# board.net
KiCad netlist of a schematic drawn in EAGLE
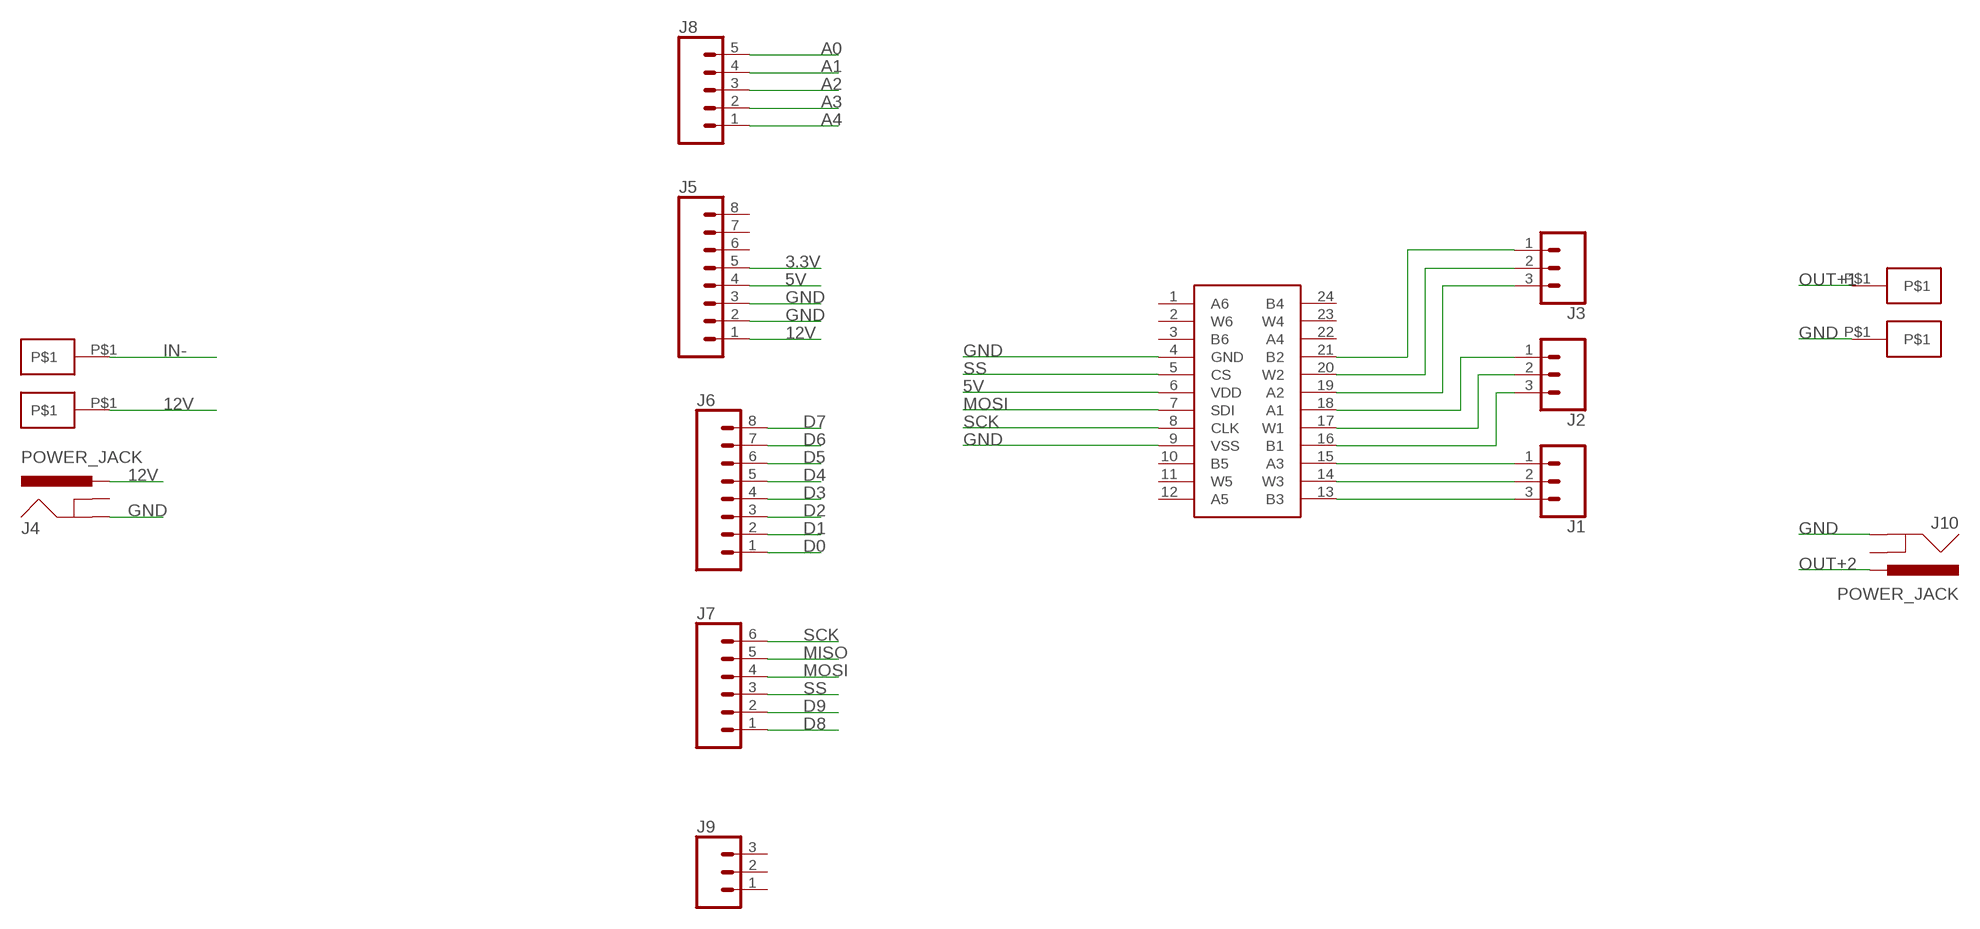
[diagram p0: schematic, sheet 1]

(export (version "E")
  (design (tool "Eeschema 10.0.6"))
  (components
    (comp (ref "J1")
      (value "CONN_03")
      (footprint "eagle-import:1X03")
      (libsource (lib "eagle-import") (part "CONN_03"))
    )
    (comp (ref "J2")
      (value "CONN_03")
      (footprint "eagle-import:1X03")
      (libsource (lib "eagle-import") (part "CONN_03"))
    )
    (comp (ref "J3")
      (value "CONN_03")
      (footprint "eagle-import:1X03")
      (libsource (lib "eagle-import") (part "CONN_03"))
    )
    (comp (ref "J4")
      (value "POWER_JACK")
      (footprint "eagle-import:POWER_JACK_PTH")
      (libsource (lib "eagle-import") (part "POWER_JACK"))
    )
    (comp (ref "J5")
      (value "CONN_08\"")
      (footprint "eagle-import:1X08")
      (libsource (lib "eagle-import") (part "CONN_08{dblquote}"))
    )
    (comp (ref "J6")
      (value "CONN_08\"")
      (footprint "eagle-import:1X08")
      (libsource (lib "eagle-import") (part "CONN_08{dblquote}"))
    )
    (comp (ref "J7")
      (value "CONN_06SILK_FEMALE_PTH")
      (footprint "eagle-import:1X06")
      (libsource (lib "eagle-import") (part "CONN_06SILK_FEMALE_PTH"))
    )
    (comp (ref "J8")
      (value "CONN_05")
      (footprint "eagle-import:1X05")
      (libsource (lib "eagle-import") (part "CONN_05"))
    )
    (comp (ref "J9")
      (value "CONN_03")
      (footprint "eagle-import:1X03")
      (libsource (lib "eagle-import") (part "CONN_03"))
    )
    (comp (ref "J10")
      (value "POWER_JACK")
      (footprint "eagle-import:POWER_JACK_PTH")
      (libsource (lib "eagle-import") (part "POWER_JACK"))
    )
    (comp (ref "U$1")
      (value "AD5206")
      (footprint "eagle-import:TSSOP24")
      (libsource (lib "eagle-import") (part "AD5206"))
    )
    (comp (ref "U$2")
      (value "M012MM-HOLE")
      (footprint "eagle-import:M01-2MM")
      (libsource (lib "eagle-import") (part "M012MM-HOLE"))
    )
    (comp (ref "U$3")
      (value "M012MM-HOLE")
      (footprint "eagle-import:M01-2MM")
      (libsource (lib "eagle-import") (part "M012MM-HOLE"))
    )
    (comp (ref "U$4")
      (value "M012MM-HOLE")
      (footprint "eagle-import:M01-2MM")
      (libsource (lib "eagle-import") (part "M012MM-HOLE"))
    )
    (comp (ref "U$5")
      (value "M012MM-HOLE")
      (footprint "eagle-import:M01-2MM")
      (libsource (lib "eagle-import") (part "M012MM-HOLE"))
    )
  )
  (nets
    (net (code "1") (name "/3.3V") (class "Default")
      (node (ref "J5") (pin "5") (pinfunction "5_5") (pintype "passive"))
    )
    (net (code "2") (name "/5V") (class "Default")
      (node (ref "J5") (pin "4") (pinfunction "4_4") (pintype "passive"))
      (node (ref "U$1") (pin "6") (pinfunction "VDD_6") (pintype "bidirectional"))
    )
    (net (code "3") (name "/12V") (class "Default")
      (node (ref "J4") (pin "PWR") (pinfunction "PWR_PWR") (pintype "bidirectional"))
      (node (ref "J5") (pin "1") (pinfunction "1_1") (pintype "passive"))
      (node (ref "U$3") (pin "P$1") (pinfunction "P$1_P$1") (pintype "bidirectional"))
    )
    (net (code "4") (name "/A0") (class "Default")
      (node (ref "J8") (pin "5") (pinfunction "5_5") (pintype "passive"))
    )
    (net (code "5") (name "/A1") (class "Default")
      (node (ref "J8") (pin "4") (pinfunction "4_4") (pintype "passive"))
    )
    (net (code "6") (name "/A2") (class "Default")
      (node (ref "J8") (pin "3") (pinfunction "3_3") (pintype "passive"))
    )
    (net (code "7") (name "/A3") (class "Default")
      (node (ref "J8") (pin "2") (pinfunction "2_2") (pintype "passive"))
    )
    (net (code "8") (name "/A4") (class "Default")
      (node (ref "J8") (pin "1") (pinfunction "1_1") (pintype "passive"))
    )
    (net (code "9") (name "/D0") (class "Default")
      (node (ref "J6") (pin "1") (pinfunction "1_1") (pintype "passive"))
    )
    (net (code "10") (name "/D1") (class "Default")
      (node (ref "J6") (pin "2") (pinfunction "2_2") (pintype "passive"))
    )
    (net (code "11") (name "/D2") (class "Default")
      (node (ref "J6") (pin "3") (pinfunction "3_3") (pintype "passive"))
    )
    (net (code "12") (name "/D3") (class "Default")
      (node (ref "J6") (pin "4") (pinfunction "4_4") (pintype "passive"))
    )
    (net (code "13") (name "/D4") (class "Default")
      (node (ref "J6") (pin "5") (pinfunction "5_5") (pintype "passive"))
    )
    (net (code "14") (name "/D5") (class "Default")
      (node (ref "J6") (pin "6") (pinfunction "6_6") (pintype "passive"))
    )
    (net (code "15") (name "/D6") (class "Default")
      (node (ref "J6") (pin "7") (pinfunction "7_7") (pintype "passive"))
    )
    (net (code "16") (name "/D7") (class "Default")
      (node (ref "J6") (pin "8") (pinfunction "8_8") (pintype "passive"))
    )
    (net (code "17") (name "/D8") (class "Default")
      (node (ref "J7") (pin "1") (pinfunction "1_1") (pintype "passive"))
    )
    (net (code "18") (name "/D9") (class "Default")
      (node (ref "J7") (pin "2") (pinfunction "2_2") (pintype "passive"))
    )
    (net (code "19") (name "/GND") (class "Default")
      (node (ref "J10") (pin "GND") (pinfunction "GND_GND") (pintype "bidirectional"))
      (node (ref "J4") (pin "GND") (pinfunction "GND_GND") (pintype "bidirectional"))
      (node (ref "J5") (pin "2") (pinfunction "2_2") (pintype "passive"))
      (node (ref "J5") (pin "3") (pinfunction "3_3") (pintype "passive"))
      (node (ref "U$1") (pin "4") (pinfunction "GND_4") (pintype "bidirectional"))
      (node (ref "U$1") (pin "9") (pinfunction "VSS_9") (pintype "bidirectional"))
      (node (ref "U$5") (pin "P$1") (pinfunction "P$1_P$1") (pintype "bidirectional"))
    )
    (net (code "20") (name "/IN-") (class "Default")
      (node (ref "U$2") (pin "P$1") (pinfunction "P$1_P$1") (pintype "bidirectional"))
    )
    (net (code "21") (name "/MISO") (class "Default")
      (node (ref "J7") (pin "5") (pinfunction "5_5") (pintype "passive"))
    )
    (net (code "22") (name "/MOSI") (class "Default")
      (node (ref "J7") (pin "4") (pinfunction "4_4") (pintype "passive"))
      (node (ref "U$1") (pin "7") (pinfunction "SDI_7") (pintype "bidirectional"))
    )
    (net (code "23") (name "/OUT+1") (class "Default")
      (node (ref "U$4") (pin "P$1") (pinfunction "P$1_P$1") (pintype "bidirectional"))
    )
    (net (code "24") (name "/OUT+2") (class "Default")
      (node (ref "J10") (pin "PWR") (pinfunction "PWR_PWR") (pintype "bidirectional"))
    )
    (net (code "25") (name "/SCK") (class "Default")
      (node (ref "J7") (pin "6") (pinfunction "6_6") (pintype "passive"))
      (node (ref "U$1") (pin "8") (pinfunction "CLK_8") (pintype "bidirectional"))
    )
    (net (code "26") (name "/SS") (class "Default")
      (node (ref "J7") (pin "3") (pinfunction "3_3") (pintype "passive"))
      (node (ref "U$1") (pin "5") (pinfunction "CS_5") (pintype "bidirectional"))
    )
    (net (code "27") (name "Net-(U$1-A1)") (class "Default")
      (node (ref "J2") (pin "1") (pinfunction "1_1") (pintype "passive"))
      (node (ref "U$1") (pin "18") (pinfunction "A1_18") (pintype "bidirectional"))
    )
    (net (code "28") (name "Net-(U$1-A2)") (class "Default")
      (node (ref "J3") (pin "3") (pinfunction "3_3") (pintype "passive"))
      (node (ref "U$1") (pin "19") (pinfunction "A2_19") (pintype "bidirectional"))
    )
    (net (code "29") (name "Net-(U$1-A3)") (class "Default")
      (node (ref "J1") (pin "1") (pinfunction "1_1") (pintype "passive"))
      (node (ref "U$1") (pin "15") (pinfunction "A3_15") (pintype "bidirectional"))
    )
    (net (code "30") (name "Net-(U$1-B1)") (class "Default")
      (node (ref "J2") (pin "3") (pinfunction "3_3") (pintype "passive"))
      (node (ref "U$1") (pin "16") (pinfunction "B1_16") (pintype "bidirectional"))
    )
    (net (code "31") (name "Net-(U$1-B2)") (class "Default")
      (node (ref "J3") (pin "1") (pinfunction "1_1") (pintype "passive"))
      (node (ref "U$1") (pin "21") (pinfunction "B2_21") (pintype "bidirectional"))
    )
    (net (code "32") (name "Net-(U$1-B3)") (class "Default")
      (node (ref "J1") (pin "3") (pinfunction "3_3") (pintype "passive"))
      (node (ref "U$1") (pin "13") (pinfunction "B3_13") (pintype "bidirectional"))
    )
    (net (code "33") (name "Net-(U$1-W1)") (class "Default")
      (node (ref "J2") (pin "2") (pinfunction "2_2") (pintype "passive"))
      (node (ref "U$1") (pin "17") (pinfunction "W1_17") (pintype "bidirectional"))
    )
    (net (code "34") (name "Net-(U$1-W2)") (class "Default")
      (node (ref "J3") (pin "2") (pinfunction "2_2") (pintype "passive"))
      (node (ref "U$1") (pin "20") (pinfunction "W2_20") (pintype "bidirectional"))
    )
    (net (code "35") (name "Net-(U$1-W3)") (class "Default")
      (node (ref "J1") (pin "2") (pinfunction "2_2") (pintype "passive"))
      (node (ref "U$1") (pin "14") (pinfunction "W3_14") (pintype "bidirectional"))
    )
    (net (code "36") (name "unconnected-(J4-PadGNDBREAK)") (class "Default")
      (node (ref "J4") (pin "GNDBREAK") (pinfunction "GNDBREAK_GNDBREAK") (pintype "bidirectional"))
    )
    (net (code "37") (name "unconnected-(J5-Pad6)") (class "Default")
      (node (ref "J5") (pin "6") (pinfunction "6_6") (pintype "passive"))
    )
    (net (code "38") (name "unconnected-(J5-Pad7)") (class "Default")
      (node (ref "J5") (pin "7") (pinfunction "7_7") (pintype "passive"))
    )
    (net (code "39") (name "unconnected-(J5-Pad8)") (class "Default")
      (node (ref "J5") (pin "8") (pinfunction "8_8") (pintype "passive"))
    )
    (net (code "40") (name "unconnected-(J9-Pad1)") (class "Default")
      (node (ref "J9") (pin "1") (pinfunction "1_1") (pintype "passive"))
    )
    (net (code "41") (name "unconnected-(J9-Pad2)") (class "Default")
      (node (ref "J9") (pin "2") (pinfunction "2_2") (pintype "passive"))
    )
    (net (code "42") (name "unconnected-(J9-Pad3)") (class "Default")
      (node (ref "J9") (pin "3") (pinfunction "3_3") (pintype "passive"))
    )
    (net (code "43") (name "unconnected-(J10-PadGNDBREAK)") (class "Default")
      (node (ref "J10") (pin "GNDBREAK") (pinfunction "GNDBREAK_GNDBREAK") (pintype "bidirectional"))
    )
    (net (code "44") (name "unconnected-(U$1-A4-Pad22)") (class "Default")
      (node (ref "U$1") (pin "22") (pinfunction "A4_22") (pintype "bidirectional"))
    )
    (net (code "45") (name "unconnected-(U$1-A5-Pad12)") (class "Default")
      (node (ref "U$1") (pin "12") (pinfunction "A5_12") (pintype "bidirectional"))
    )
    (net (code "46") (name "unconnected-(U$1-A6-Pad1)") (class "Default")
      (node (ref "U$1") (pin "1") (pinfunction "A6_1") (pintype "bidirectional"))
    )
    (net (code "47") (name "unconnected-(U$1-B4-Pad24)") (class "Default")
      (node (ref "U$1") (pin "24") (pinfunction "B4_24") (pintype "bidirectional"))
    )
    (net (code "48") (name "unconnected-(U$1-B5-Pad10)") (class "Default")
      (node (ref "U$1") (pin "10") (pinfunction "B5_10") (pintype "bidirectional"))
    )
    (net (code "49") (name "unconnected-(U$1-B6-Pad3)") (class "Default")
      (node (ref "U$1") (pin "3") (pinfunction "B6_3") (pintype "bidirectional"))
    )
    (net (code "50") (name "unconnected-(U$1-W4-Pad23)") (class "Default")
      (node (ref "U$1") (pin "23") (pinfunction "W4_23") (pintype "bidirectional"))
    )
    (net (code "51") (name "unconnected-(U$1-W5-Pad11)") (class "Default")
      (node (ref "U$1") (pin "11") (pinfunction "W5_11") (pintype "bidirectional"))
    )
    (net (code "52") (name "unconnected-(U$1-W6-Pad2)") (class "Default")
      (node (ref "U$1") (pin "2") (pinfunction "W6_2") (pintype "bidirectional"))
    )
  )
)
